# IO_module.net
KiCad netlist of a schematic drawn in EAGLE
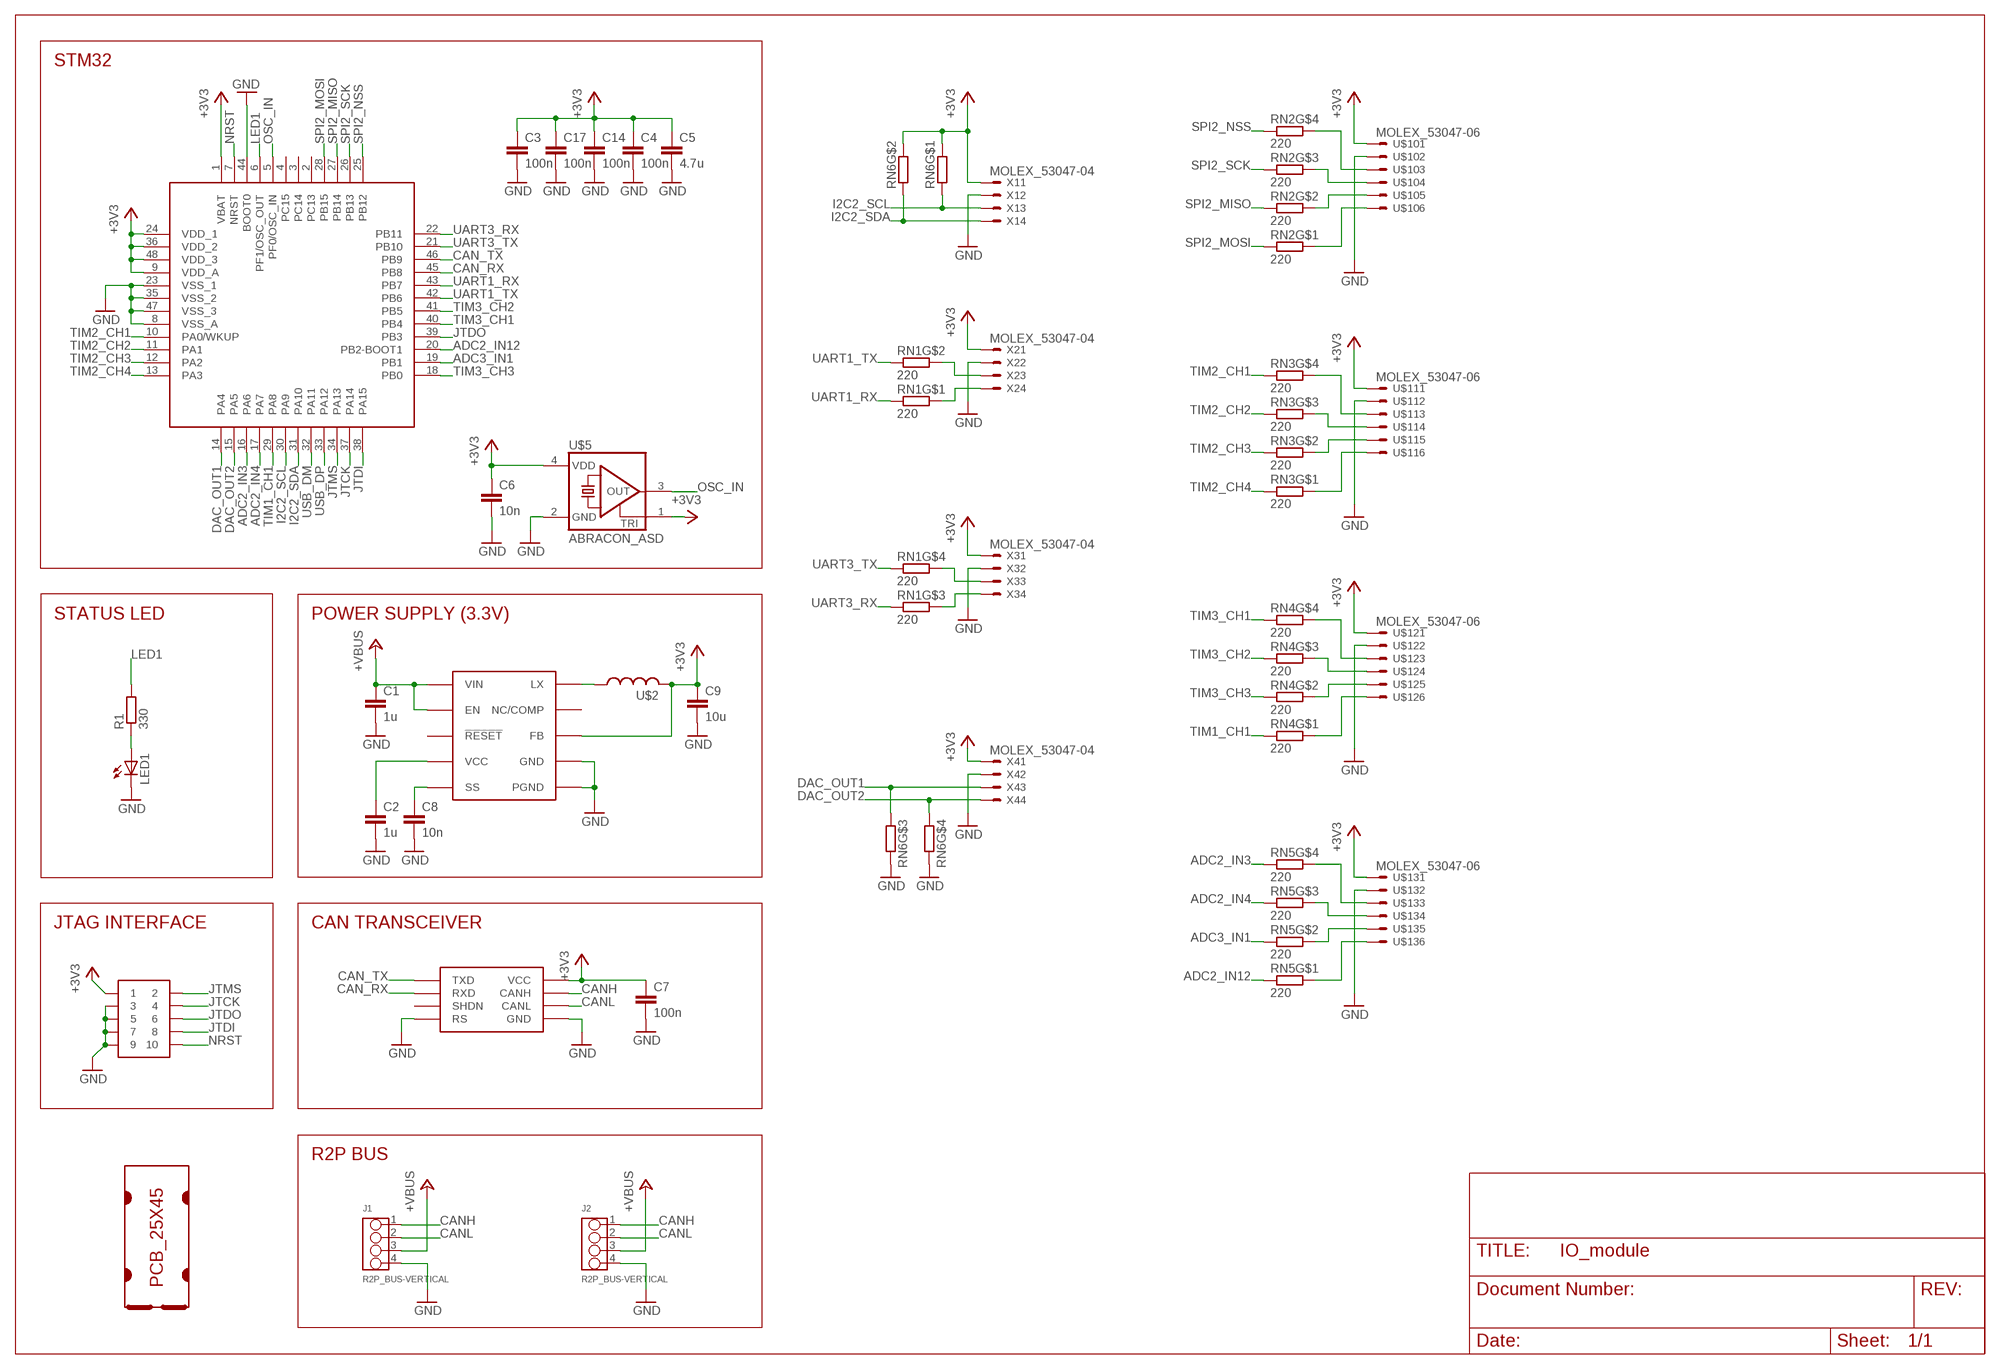
[diagram p0: schematic, sheet 1]

(export (version "E")
  (design (tool "Eeschema 10.0.6"))
  (components
    (comp (ref "C1")
      (value "1u")
      (footprint "eagle-import:C1206")
      (libsource (lib "eagle-import") (part "C1206"))
    )
    (comp (ref "C2")
      (value "1u")
      (footprint "eagle-import:C0603")
      (libsource (lib "eagle-import") (part "C0603"))
    )
    (comp (ref "C3")
      (value "100n")
      (footprint "eagle-import:C0603")
      (libsource (lib "eagle-import") (part "C0603"))
    )
    (comp (ref "C4")
      (value "100n")
      (footprint "eagle-import:C0603")
      (libsource (lib "eagle-import") (part "C0603"))
    )
    (comp (ref "C5")
      (value "4.7u")
      (footprint "eagle-import:C0805")
      (libsource (lib "eagle-import") (part "C0805"))
    )
    (comp (ref "C6")
      (value "10n")
      (footprint "eagle-import:C0603")
      (libsource (lib "eagle-import") (part "C0603"))
    )
    (comp (ref "C7")
      (value "100n")
      (footprint "eagle-import:C0603")
      (libsource (lib "eagle-import") (part "C0603"))
    )
    (comp (ref "C8")
      (value "10n")
      (footprint "eagle-import:C0603")
      (libsource (lib "eagle-import") (part "C0603"))
    )
    (comp (ref "C9")
      (value "10u")
      (footprint "eagle-import:C0805")
      (libsource (lib "eagle-import") (part "C0805"))
    )
    (comp (ref "C14")
      (value "100n")
      (footprint "eagle-import:C0603")
      (libsource (lib "eagle-import") (part "C0603"))
    )
    (comp (ref "C17")
      (value "100n")
      (footprint "eagle-import:C0603")
      (libsource (lib "eagle-import") (part "C0603"))
    )
    (comp (ref "J1")
      (value "R2P_BUS-VERTICAL")
      (footprint "eagle-import:OPL-EAGLE-LIBRARY_4P-2.0")
      (libsource (lib "eagle-import") (part "R2P_BUS-VERTICAL"))
    )
    (comp (ref "J2")
      (value "R2P_BUS-VERTICAL")
      (footprint "eagle-import:OPL-EAGLE-LIBRARY_4P-2.0")
      (libsource (lib "eagle-import") (part "R2P_BUS-VERTICAL"))
    )
    (comp (ref "LED1")
      (value "LED0805")
      (footprint "eagle-import:CHIPLED_0805")
      (libsource (lib "eagle-import") (part "LED0805"))
    )
    (comp (ref "R1")
      (value "330")
      (footprint "eagle-import:R0603")
      (libsource (lib "eagle-import") (part "R0603"))
    )
    (comp (ref "RN1")
      (value "220")
      (footprint "eagle-import:RNET4_1206")
      (libsource (lib "eagle-import") (part "RNETWORK_4-1206"))
    )
    (comp (ref "RN2")
      (value "220")
      (footprint "eagle-import:RNET4_1206")
      (libsource (lib "eagle-import") (part "RNETWORK_4-1206"))
    )
    (comp (ref "RN3")
      (value "220")
      (footprint "eagle-import:RNET4_1206")
      (libsource (lib "eagle-import") (part "RNETWORK_4-1206"))
    )
    (comp (ref "RN4")
      (value "220")
      (footprint "eagle-import:RNET4_1206")
      (libsource (lib "eagle-import") (part "RNETWORK_4-1206"))
    )
    (comp (ref "RN5")
      (value "220")
      (footprint "eagle-import:RNET4_1206")
      (libsource (lib "eagle-import") (part "RNETWORK_4-1206"))
    )
    (comp (ref "RN6")
      (value "RNETWORK_4-1206")
      (footprint "eagle-import:RNET4_1206")
      (libsource (lib "eagle-import") (part "RNETWORK_4-1206"))
    )
    (comp (ref "SOT1")
      (value "MAX3051EKA")
      (footprint "eagle-import:SOT23-8L")
      (libsource (lib "eagle-import") (part "MAX3051EKA"))
    )
    (comp (ref "U$1")
      (value "PCB_25X45")
      (footprint "eagle-import:25X45")
      (libsource (lib "eagle-import") (part "PCB_25X45"))
    )
    (comp (ref "U$2")
      (value "LPS4018")
      (footprint "eagle-import:COILCRAFT_LPS4018")
      (libsource (lib "eagle-import") (part "LPS4018"))
    )
    (comp (ref "U$3")
      (value "MAX17501")
      (footprint "eagle-import:TDFN-10")
      (libsource (lib "eagle-import") (part "MAX17501"))
    )
    (comp (ref "U$4")
      (value "JTAG-TH")
      (footprint "eagle-import:SAMTEC_FTSH-105-TH")
      (libsource (lib "eagle-import") (part "JTAG-TH"))
    )
    (comp (ref "U$5")
      (value "ABRACON_ASD")
      (footprint "eagle-import:ABRACON_2.5X2")
      (libsource (lib "eagle-import") (part "ABRACON_ASD"))
    )
    (comp (ref "U$6")
      (value "STM32F303CTX")
      (footprint "eagle-import:LQFP48")
      (libsource (lib "eagle-import") (part "STM32F303CTX"))
    )
    (comp (ref "U$10")
      (value "MOLEX_53047-06")
      (footprint "eagle-import:MOLEX_53047-06")
      (libsource (lib "eagle-import") (part "MOLEX_53?-06047"))
    )
    (comp (ref "U$11")
      (value "MOLEX_53047-06")
      (footprint "eagle-import:MOLEX_53047-06")
      (libsource (lib "eagle-import") (part "MOLEX_53?-06047"))
    )
    (comp (ref "U$12")
      (value "MOLEX_53047-06")
      (footprint "eagle-import:MOLEX_53047-06")
      (libsource (lib "eagle-import") (part "MOLEX_53?-06047"))
    )
    (comp (ref "U$13")
      (value "MOLEX_53047-06")
      (footprint "eagle-import:MOLEX_53047-06")
      (libsource (lib "eagle-import") (part "MOLEX_53?-06047"))
    )
    (comp (ref "X1")
      (value "MOLEX_53047-04")
      (footprint "eagle-import:MOLEX_53047-04")
      (fields (field (name "MF") "WALDOM/MOLEX") (field (name "MPN") "53047-0410"))
      (libsource (lib "eagle-import") (part "MOLEX_53?-04047"))
    )
    (comp (ref "X2")
      (value "MOLEX_53047-04")
      (footprint "eagle-import:MOLEX_53047-04")
      (fields (field (name "MF") "WALDOM/MOLEX") (field (name "MPN") "53047-0410"))
      (libsource (lib "eagle-import") (part "MOLEX_53?-04047"))
    )
    (comp (ref "X3")
      (value "MOLEX_53047-04")
      (footprint "eagle-import:MOLEX_53047-04")
      (fields (field (name "MF") "WALDOM/MOLEX") (field (name "MPN") "53047-0410"))
      (libsource (lib "eagle-import") (part "MOLEX_53?-04047"))
    )
    (comp (ref "X4")
      (value "MOLEX_53047-04")
      (footprint "eagle-import:MOLEX_53047-04")
      (fields (field (name "MF") "WALDOM/MOLEX") (field (name "MPN") "53047-0410"))
      (libsource (lib "eagle-import") (part "MOLEX_53?-04047"))
    )
  )
  (nets
    (net (code "1") (name "+3V3") (class "Default")
      (node (ref "C14") (pin "1") (pinfunction "1_1") (pintype "passive"))
      (node (ref "C17") (pin "1") (pinfunction "1_1") (pintype "passive"))
      (node (ref "C3") (pin "1") (pinfunction "1_1") (pintype "passive"))
      (node (ref "C4") (pin "1") (pinfunction "1_1") (pintype "passive"))
      (node (ref "C5") (pin "1") (pinfunction "1_1") (pintype "passive"))
      (node (ref "C6") (pin "1") (pinfunction "1_1") (pintype "passive"))
      (node (ref "C7") (pin "1") (pinfunction "1_1") (pintype "passive"))
      (node (ref "C9") (pin "1") (pinfunction "1_1") (pintype "passive"))
      (node (ref "RN6") (pin "7") (pinfunction "2_7") (pintype "passive"))
      (node (ref "RN6") (pin "8") (pinfunction "2_8") (pintype "passive"))
      (node (ref "SOT1") (pin "3") (pinfunction "VCC_3") (pintype "bidirectional"))
      (node (ref "U$10") (pin "1") (pinfunction "S_1") (pintype "passive"))
      (node (ref "U$11") (pin "1") (pinfunction "S_1") (pintype "passive"))
      (node (ref "U$12") (pin "1") (pinfunction "S_1") (pintype "passive"))
      (node (ref "U$13") (pin "1") (pinfunction "S_1") (pintype "passive"))
      (node (ref "U$2") (pin "P$2") (pinfunction "2_P$2") (pintype "passive"))
      (node (ref "U$3") (pin "P$5") (pinfunction "FB_P$5") (pintype "bidirectional"))
      (node (ref "U$4") (pin "1") (pinfunction "1_1") (pintype "bidirectional"))
      (node (ref "U$5") (pin "1") (pinfunction "TRI_1") (pintype "input"))
      (node (ref "U$5") (pin "4") (pinfunction "VDD_4") (pintype "power_in"))
      (node (ref "U$6") (pin "1") (pinfunction "VBAT_1") (pintype "bidirectional"))
      (node (ref "U$6") (pin "24") (pinfunction "VDD_1_24") (pintype "bidirectional"))
      (node (ref "U$6") (pin "36") (pinfunction "VDD_2_36") (pintype "bidirectional"))
      (node (ref "U$6") (pin "48") (pinfunction "VDD_3_48") (pintype "bidirectional"))
      (node (ref "U$6") (pin "9") (pinfunction "VDD_A_9") (pintype "bidirectional"))
      (node (ref "X1") (pin "1") (pinfunction "S_1") (pintype "passive"))
      (node (ref "X2") (pin "1") (pinfunction "S_1") (pintype "passive"))
      (node (ref "X3") (pin "1") (pinfunction "S_1") (pintype "passive"))
      (node (ref "X4") (pin "1") (pinfunction "S_1") (pintype "passive"))
    )
    (net (code "2") (name "+VBUS") (class "Default")
      (node (ref "C1") (pin "1") (pinfunction "1_1") (pintype "passive"))
      (node (ref "J1") (pin "3") (pinfunction "3_3") (pintype "bidirectional"))
      (node (ref "J2") (pin "3") (pinfunction "3_3") (pintype "bidirectional"))
      (node (ref "U$3") (pin "P$2") (pinfunction "VIN_P$2") (pintype "bidirectional"))
      (node (ref "U$3") (pin "P$3") (pinfunction "EN_P$3") (pintype "bidirectional"))
    )
    (net (code "3") (name "/ADC2_IN3") (class "Default")
      (node (ref "RN5") (pin "4") (pinfunction "1_4") (pintype "passive"))
      (node (ref "U$6") (pin "16") (pinfunction "PA6_16") (pintype "bidirectional"))
    )
    (net (code "4") (name "/ADC2_IN4") (class "Default")
      (node (ref "RN5") (pin "3") (pinfunction "1_3") (pintype "passive"))
      (node (ref "U$6") (pin "17") (pinfunction "PA7_17") (pintype "bidirectional"))
    )
    (net (code "5") (name "/ADC2_IN12") (class "Default")
      (node (ref "RN5") (pin "1") (pinfunction "1_1") (pintype "passive"))
      (node (ref "U$6") (pin "20") (pinfunction "PB2-BOOT1_20") (pintype "bidirectional"))
    )
    (net (code "6") (name "/ADC3_IN1") (class "Default")
      (node (ref "RN5") (pin "2") (pinfunction "1_2") (pintype "passive"))
      (node (ref "U$6") (pin "19") (pinfunction "PB1_19") (pintype "bidirectional"))
    )
    (net (code "7") (name "/CANH") (class "Default")
      (node (ref "J1") (pin "1") (pinfunction "1_1") (pintype "bidirectional"))
      (node (ref "J2") (pin "1") (pinfunction "1_1") (pintype "bidirectional"))
      (node (ref "SOT1") (pin "7") (pinfunction "CANH_7") (pintype "bidirectional"))
    )
    (net (code "8") (name "/CANL") (class "Default")
      (node (ref "J1") (pin "2") (pinfunction "2_2") (pintype "bidirectional"))
      (node (ref "J2") (pin "2") (pinfunction "2_2") (pintype "bidirectional"))
      (node (ref "SOT1") (pin "6") (pinfunction "CANL_6") (pintype "bidirectional"))
    )
    (net (code "9") (name "/CAN_RX") (class "Default")
      (node (ref "SOT1") (pin "4") (pinfunction "RXD_4") (pintype "bidirectional"))
      (node (ref "U$6") (pin "45") (pinfunction "PB8_45") (pintype "bidirectional"))
    )
    (net (code "10") (name "/CAN_TX") (class "Default")
      (node (ref "SOT1") (pin "1") (pinfunction "TXD_1") (pintype "bidirectional"))
      (node (ref "U$6") (pin "46") (pinfunction "PB9_46") (pintype "bidirectional"))
    )
    (net (code "11") (name "/DAC_OUT1") (class "Default")
      (node (ref "RN6") (pin "3") (pinfunction "1_3") (pintype "passive"))
      (node (ref "U$6") (pin "14") (pinfunction "PA4_14") (pintype "bidirectional"))
      (node (ref "X4") (pin "3") (pinfunction "S_3") (pintype "passive"))
    )
    (net (code "12") (name "/DAC_OUT2") (class "Default")
      (node (ref "RN6") (pin "4") (pinfunction "1_4") (pintype "passive"))
      (node (ref "U$6") (pin "15") (pinfunction "PA5_15") (pintype "bidirectional"))
      (node (ref "X4") (pin "4") (pinfunction "S_4") (pintype "passive"))
    )
    (net (code "13") (name "/I2C2_SCL") (class "Default")
      (node (ref "RN6") (pin "1") (pinfunction "1_1") (pintype "passive"))
      (node (ref "U$6") (pin "30") (pinfunction "PA9_30") (pintype "bidirectional"))
      (node (ref "X1") (pin "3") (pinfunction "S_3") (pintype "passive"))
    )
    (net (code "14") (name "/I2C2_SDA") (class "Default")
      (node (ref "RN6") (pin "2") (pinfunction "1_2") (pintype "passive"))
      (node (ref "U$6") (pin "31") (pinfunction "PA10_31") (pintype "bidirectional"))
      (node (ref "X1") (pin "4") (pinfunction "S_4") (pintype "passive"))
    )
    (net (code "15") (name "/JTCK") (class "Default")
      (node (ref "U$4") (pin "4") (pinfunction "4_4") (pintype "bidirectional"))
      (node (ref "U$6") (pin "37") (pinfunction "PA14_37") (pintype "bidirectional"))
    )
    (net (code "16") (name "/JTDI") (class "Default")
      (node (ref "U$4") (pin "8") (pinfunction "8_8") (pintype "bidirectional"))
      (node (ref "U$6") (pin "38") (pinfunction "PA15_38") (pintype "bidirectional"))
    )
    (net (code "17") (name "/JTDO") (class "Default")
      (node (ref "U$4") (pin "6") (pinfunction "6_6") (pintype "bidirectional"))
      (node (ref "U$6") (pin "39") (pinfunction "PB3_39") (pintype "bidirectional"))
    )
    (net (code "18") (name "/JTMS") (class "Default")
      (node (ref "U$4") (pin "2") (pinfunction "2_2") (pintype "bidirectional"))
      (node (ref "U$6") (pin "34") (pinfunction "PA13_34") (pintype "bidirectional"))
    )
    (net (code "19") (name "/LED1") (class "Default")
      (node (ref "R1") (pin "2") (pinfunction "2_2") (pintype "passive"))
      (node (ref "U$6") (pin "6") (pinfunction "PF1/OSC_OUT_6") (pintype "bidirectional"))
    )
    (net (code "20") (name "/NRST") (class "Default")
      (node (ref "U$4") (pin "10") (pinfunction "10_10") (pintype "bidirectional"))
      (node (ref "U$6") (pin "7") (pinfunction "NRST_7") (pintype "bidirectional"))
    )
    (net (code "21") (name "/OSC_IN") (class "Default")
      (node (ref "U$5") (pin "3") (pinfunction "OUT_3") (pintype "output"))
      (node (ref "U$6") (pin "5") (pinfunction "PF0/OSC_IN_5") (pintype "bidirectional"))
    )
    (net (code "22") (name "/SPI2_MISO") (class "Default")
      (node (ref "RN2") (pin "2") (pinfunction "1_2") (pintype "passive"))
      (node (ref "U$6") (pin "27") (pinfunction "PB14_27") (pintype "bidirectional"))
    )
    (net (code "23") (name "/SPI2_MOSI") (class "Default")
      (node (ref "RN2") (pin "1") (pinfunction "1_1") (pintype "passive"))
      (node (ref "U$6") (pin "28") (pinfunction "PB15_28") (pintype "bidirectional"))
    )
    (net (code "24") (name "/SPI2_NSS") (class "Default")
      (node (ref "RN2") (pin "4") (pinfunction "1_4") (pintype "passive"))
      (node (ref "U$6") (pin "25") (pinfunction "PB12_25") (pintype "bidirectional"))
    )
    (net (code "25") (name "/SPI2_SCK") (class "Default")
      (node (ref "RN2") (pin "3") (pinfunction "1_3") (pintype "passive"))
      (node (ref "U$6") (pin "26") (pinfunction "PB13_26") (pintype "bidirectional"))
    )
    (net (code "26") (name "/TIM1_CH1") (class "Default")
      (node (ref "RN4") (pin "1") (pinfunction "1_1") (pintype "passive"))
      (node (ref "U$6") (pin "29") (pinfunction "PA8_29") (pintype "bidirectional"))
    )
    (net (code "27") (name "/TIM2_CH1") (class "Default")
      (node (ref "RN3") (pin "4") (pinfunction "1_4") (pintype "passive"))
      (node (ref "U$6") (pin "10") (pinfunction "PA0/WKUP_10") (pintype "bidirectional"))
    )
    (net (code "28") (name "/TIM2_CH2") (class "Default")
      (node (ref "RN3") (pin "3") (pinfunction "1_3") (pintype "passive"))
      (node (ref "U$6") (pin "11") (pinfunction "PA1_11") (pintype "bidirectional"))
    )
    (net (code "29") (name "/TIM2_CH3") (class "Default")
      (node (ref "RN3") (pin "2") (pinfunction "1_2") (pintype "passive"))
      (node (ref "U$6") (pin "12") (pinfunction "PA2_12") (pintype "bidirectional"))
    )
    (net (code "30") (name "/TIM2_CH4") (class "Default")
      (node (ref "RN3") (pin "1") (pinfunction "1_1") (pintype "passive"))
      (node (ref "U$6") (pin "13") (pinfunction "PA3_13") (pintype "bidirectional"))
    )
    (net (code "31") (name "/TIM3_CH1") (class "Default")
      (node (ref "RN4") (pin "4") (pinfunction "1_4") (pintype "passive"))
      (node (ref "U$6") (pin "40") (pinfunction "PB4_40") (pintype "bidirectional"))
    )
    (net (code "32") (name "/TIM3_CH2") (class "Default")
      (node (ref "RN4") (pin "3") (pinfunction "1_3") (pintype "passive"))
      (node (ref "U$6") (pin "41") (pinfunction "PB5_41") (pintype "bidirectional"))
    )
    (net (code "33") (name "/TIM3_CH3") (class "Default")
      (node (ref "RN4") (pin "2") (pinfunction "1_2") (pintype "passive"))
      (node (ref "U$6") (pin "18") (pinfunction "PB0_18") (pintype "bidirectional"))
    )
    (net (code "34") (name "/UART1_RX") (class "Default")
      (node (ref "RN1") (pin "1") (pinfunction "1_1") (pintype "passive"))
      (node (ref "U$6") (pin "43") (pinfunction "PB7_43") (pintype "bidirectional"))
    )
    (net (code "35") (name "/UART1_TX") (class "Default")
      (node (ref "RN1") (pin "2") (pinfunction "1_2") (pintype "passive"))
      (node (ref "U$6") (pin "42") (pinfunction "PB6_42") (pintype "bidirectional"))
    )
    (net (code "36") (name "/UART3_RX") (class "Default")
      (node (ref "RN1") (pin "3") (pinfunction "1_3") (pintype "passive"))
      (node (ref "U$6") (pin "22") (pinfunction "PB11_22") (pintype "bidirectional"))
    )
    (net (code "37") (name "/UART3_TX") (class "Default")
      (node (ref "RN1") (pin "4") (pinfunction "1_4") (pintype "passive"))
      (node (ref "U$6") (pin "21") (pinfunction "PB10_21") (pintype "bidirectional"))
    )
    (net (code "38") (name "/USB_DM") (class "Default")
      (node (ref "U$6") (pin "32") (pinfunction "PA11_32") (pintype "bidirectional"))
    )
    (net (code "39") (name "/USB_DP") (class "Default")
      (node (ref "U$6") (pin "33") (pinfunction "PA12_33") (pintype "bidirectional"))
    )
    (net (code "40") (name "GND") (class "Default")
      (node (ref "C1") (pin "2") (pinfunction "2_2") (pintype "passive"))
      (node (ref "C14") (pin "2") (pinfunction "2_2") (pintype "passive"))
      (node (ref "C17") (pin "2") (pinfunction "2_2") (pintype "passive"))
      (node (ref "C2") (pin "2") (pinfunction "2_2") (pintype "passive"))
      (node (ref "C3") (pin "2") (pinfunction "2_2") (pintype "passive"))
      (node (ref "C4") (pin "2") (pinfunction "2_2") (pintype "passive"))
      (node (ref "C5") (pin "2") (pinfunction "2_2") (pintype "passive"))
      (node (ref "C6") (pin "2") (pinfunction "2_2") (pintype "passive"))
      (node (ref "C7") (pin "2") (pinfunction "2_2") (pintype "passive"))
      (node (ref "C8") (pin "2") (pinfunction "2_2") (pintype "passive"))
      (node (ref "C9") (pin "2") (pinfunction "2_2") (pintype "passive"))
      (node (ref "J1") (pin "4") (pinfunction "4_4") (pintype "bidirectional"))
      (node (ref "J2") (pin "4") (pinfunction "4_4") (pintype "bidirectional"))
      (node (ref "LED1") (pin "C") (pinfunction "C_C") (pintype "passive"))
      (node (ref "RN6") (pin "5") (pinfunction "2_5") (pintype "passive"))
      (node (ref "RN6") (pin "6") (pinfunction "2_6") (pintype "passive"))
      (node (ref "SOT1") (pin "2") (pinfunction "GND_2") (pintype "bidirectional"))
      (node (ref "SOT1") (pin "8") (pinfunction "RS_8") (pintype "bidirectional"))
      (node (ref "U$10") (pin "2") (pinfunction "S_2") (pintype "passive"))
      (node (ref "U$11") (pin "2") (pinfunction "S_2") (pintype "passive"))
      (node (ref "U$12") (pin "2") (pinfunction "S_2") (pintype "passive"))
      (node (ref "U$13") (pin "2") (pinfunction "S_2") (pintype "passive"))
      (node (ref "U$3") (pin "P$1") (pinfunction "PGND_P$1") (pintype "bidirectional"))
      (node (ref "U$3") (pin "P$11") (pinfunction "PGND_P$11") (pintype "bidirectional"))
      (node (ref "U$3") (pin "P$9") (pinfunction "GND_P$9") (pintype "bidirectional"))
      (node (ref "U$4") (pin "3") (pinfunction "3_3") (pintype "bidirectional"))
      (node (ref "U$4") (pin "5") (pinfunction "5_5") (pintype "bidirectional"))
      (node (ref "U$4") (pin "7") (pinfunction "7_7") (pintype "bidirectional"))
      (node (ref "U$4") (pin "9") (pinfunction "9_9") (pintype "bidirectional"))
      (node (ref "U$5") (pin "2") (pinfunction "GND_2") (pintype "power_in"))
      (node (ref "U$6") (pin "23") (pinfunction "VSS_1_23") (pintype "bidirectional"))
      (node (ref "U$6") (pin "35") (pinfunction "VSS_2_35") (pintype "bidirectional"))
      (node (ref "U$6") (pin "44") (pinfunction "BOOT0_44") (pintype "bidirectional"))
      (node (ref "U$6") (pin "47") (pinfunction "VSS_3_47") (pintype "bidirectional"))
      (node (ref "U$6") (pin "8") (pinfunction "VSS_A_8") (pintype "bidirectional"))
      (node (ref "X1") (pin "2") (pinfunction "S_2") (pintype "passive"))
      (node (ref "X2") (pin "2") (pinfunction "S_2") (pintype "passive"))
      (node (ref "X3") (pin "2") (pinfunction "S_2") (pintype "passive"))
      (node (ref "X4") (pin "2") (pinfunction "S_2") (pintype "passive"))
    )
    (net (code "41") (name "Net-(LED1-PadA)") (class "Default")
      (node (ref "LED1") (pin "A") (pinfunction "A_A") (pintype "passive"))
      (node (ref "R1") (pin "1") (pinfunction "1_1") (pintype "passive"))
    )
    (net (code "42") (name "Net-(RN1A-2)") (class "Default")
      (node (ref "RN1") (pin "8") (pinfunction "2_8") (pintype "passive"))
      (node (ref "X2") (pin "4") (pinfunction "S_4") (pintype "passive"))
    )
    (net (code "43") (name "Net-(RN1B-2)") (class "Default")
      (node (ref "RN1") (pin "7") (pinfunction "2_7") (pintype "passive"))
      (node (ref "X2") (pin "3") (pinfunction "S_3") (pintype "passive"))
    )
    (net (code "44") (name "Net-(RN1C-2)") (class "Default")
      (node (ref "RN1") (pin "6") (pinfunction "2_6") (pintype "passive"))
      (node (ref "X3") (pin "4") (pinfunction "S_4") (pintype "passive"))
    )
    (net (code "45") (name "Net-(RN1D-2)") (class "Default")
      (node (ref "RN1") (pin "5") (pinfunction "2_5") (pintype "passive"))
      (node (ref "X3") (pin "3") (pinfunction "S_3") (pintype "passive"))
    )
    (net (code "46") (name "Net-(RN2A-2)") (class "Default")
      (node (ref "RN2") (pin "8") (pinfunction "2_8") (pintype "passive"))
      (node (ref "U$10") (pin "6") (pinfunction "S_6") (pintype "passive"))
    )
    (net (code "47") (name "Net-(RN2B-2)") (class "Default")
      (node (ref "RN2") (pin "7") (pinfunction "2_7") (pintype "passive"))
      (node (ref "U$10") (pin "5") (pinfunction "S_5") (pintype "passive"))
    )
    (net (code "48") (name "Net-(RN2C-2)") (class "Default")
      (node (ref "RN2") (pin "6") (pinfunction "2_6") (pintype "passive"))
      (node (ref "U$10") (pin "4") (pinfunction "S_4") (pintype "passive"))
    )
    (net (code "49") (name "Net-(RN2D-2)") (class "Default")
      (node (ref "RN2") (pin "5") (pinfunction "2_5") (pintype "passive"))
      (node (ref "U$10") (pin "3") (pinfunction "S_3") (pintype "passive"))
    )
    (net (code "50") (name "Net-(RN3A-2)") (class "Default")
      (node (ref "RN3") (pin "8") (pinfunction "2_8") (pintype "passive"))
      (node (ref "U$11") (pin "6") (pinfunction "S_6") (pintype "passive"))
    )
    (net (code "51") (name "Net-(RN3B-2)") (class "Default")
      (node (ref "RN3") (pin "7") (pinfunction "2_7") (pintype "passive"))
      (node (ref "U$11") (pin "5") (pinfunction "S_5") (pintype "passive"))
    )
    (net (code "52") (name "Net-(RN3C-2)") (class "Default")
      (node (ref "RN3") (pin "6") (pinfunction "2_6") (pintype "passive"))
      (node (ref "U$11") (pin "4") (pinfunction "S_4") (pintype "passive"))
    )
    (net (code "53") (name "Net-(RN3D-2)") (class "Default")
      (node (ref "RN3") (pin "5") (pinfunction "2_5") (pintype "passive"))
      (node (ref "U$11") (pin "3") (pinfunction "S_3") (pintype "passive"))
    )
    (net (code "54") (name "Net-(RN4A-2)") (class "Default")
      (node (ref "RN4") (pin "8") (pinfunction "2_8") (pintype "passive"))
      (node (ref "U$12") (pin "6") (pinfunction "S_6") (pintype "passive"))
    )
    (net (code "55") (name "Net-(RN4B-2)") (class "Default")
      (node (ref "RN4") (pin "7") (pinfunction "2_7") (pintype "passive"))
      (node (ref "U$12") (pin "5") (pinfunction "S_5") (pintype "passive"))
    )
    (net (code "56") (name "Net-(RN4C-2)") (class "Default")
      (node (ref "RN4") (pin "6") (pinfunction "2_6") (pintype "passive"))
      (node (ref "U$12") (pin "4") (pinfunction "S_4") (pintype "passive"))
    )
    (net (code "57") (name "Net-(RN4D-2)") (class "Default")
      (node (ref "RN4") (pin "5") (pinfunction "2_5") (pintype "passive"))
      (node (ref "U$12") (pin "3") (pinfunction "S_3") (pintype "passive"))
    )
    (net (code "58") (name "Net-(RN5A-2)") (class "Default")
      (node (ref "RN5") (pin "8") (pinfunction "2_8") (pintype "passive"))
      (node (ref "U$13") (pin "6") (pinfunction "S_6") (pintype "passive"))
    )
    (net (code "59") (name "Net-(RN5B-2)") (class "Default")
      (node (ref "RN5") (pin "7") (pinfunction "2_7") (pintype "passive"))
      (node (ref "U$13") (pin "5") (pinfunction "S_5") (pintype "passive"))
    )
    (net (code "60") (name "Net-(RN5C-2)") (class "Default")
      (node (ref "RN5") (pin "6") (pinfunction "2_6") (pintype "passive"))
      (node (ref "U$13") (pin "4") (pinfunction "S_4") (pintype "passive"))
    )
    (net (code "61") (name "Net-(RN5D-2)") (class "Default")
      (node (ref "RN5") (pin "5") (pinfunction "2_5") (pintype "passive"))
      (node (ref "U$13") (pin "3") (pinfunction "S_3") (pintype "passive"))
    )
    (net (code "62") (name "Net-(U$2-1)") (class "Default")
      (node (ref "U$2") (pin "P$1") (pinfunction "1_P$1") (pintype "passive"))
      (node (ref "U$3") (pin "P$10") (pinfunction "LX_P$10") (pintype "bidirectional"))
    )
    (net (code "63") (name "Net-(U$3-SS)") (class "Default")
      (node (ref "C8") (pin "1") (pinfunction "1_1") (pintype "passive"))
      (node (ref "U$3") (pin "P$6") (pinfunction "SS_P$6") (pintype "bidirectional"))
    )
    (net (code "64") (name "Net-(U$3-VCC)") (class "Default")
      (node (ref "C2") (pin "1") (pinfunction "1_1") (pintype "passive"))
      (node (ref "U$3") (pin "P$4") (pinfunction "VCC_P$4") (pintype "bidirectional"))
    )
    (net (code "65") (name "unconnected-(SOT1-SHDN-Pad5)") (class "Default")
      (node (ref "SOT1") (pin "5") (pinfunction "SHDN_5") (pintype "bidirectional"))
    )
    (net (code "66") (name "unconnected-(U$3-NC{slash}COMP-PadP$7)") (class "Default")
      (node (ref "U$3") (pin "P$7") (pinfunction "NC/COMP_P$7") (pintype "bidirectional"))
    )
    (net (code "67") (name "unconnected-(U$3-~{RESET}-PadP$8)") (class "Default")
      (node (ref "U$3") (pin "P$8") (pinfunction "~{RESET}_P$8") (pintype "bidirectional"))
    )
    (net (code "68") (name "unconnected-(U$6-PC13-Pad2)") (class "Default")
      (node (ref "U$6") (pin "2") (pinfunction "PC13_2") (pintype "bidirectional"))
    )
    (net (code "69") (name "unconnected-(U$6-PC14-Pad3)") (class "Default")
      (node (ref "U$6") (pin "3") (pinfunction "PC14_3") (pintype "bidirectional"))
    )
    (net (code "70") (name "unconnected-(U$6-PC15-Pad4)") (class "Default")
      (node (ref "U$6") (pin "4") (pinfunction "PC15_4") (pintype "bidirectional"))
    )
  )
)
